# H_Bridge.net
KiCad netlist of a schematic drawn in Altium Designer
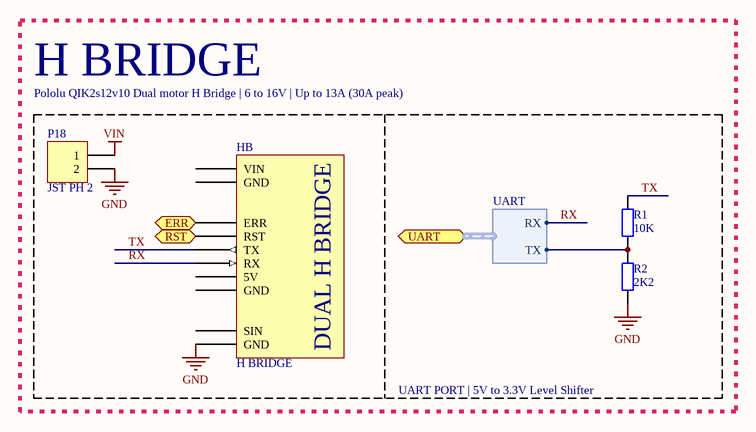
[diagram p0: H Bridge.SchDoc]

(export (version "E")
  (design (tool "Eeschema 10.0.6"))
  (components
    (comp (ref "HB")
      (value "H BRIDGE")
      (footprint "POLOLU-QIK-2S12V10-BOTTOM")
      (description "POLOLU QIK 2S12V10 DUAL H BRIDGE")
      (libsource (lib "CustomLibrary") (part "POLOLU-QIK-2S12V10"))
    )
    (comp (ref "P18")
      (value "JST PH 2")
      (footprint "B2B-PH-K")
      (libsource (lib "CustomLibrary") (part "JST PH 2"))
    )
    (comp (ref "R1") (value "10K") (footprint "RES1206") (libsource (lib "CustomLibrary") (part "RES")))
    (comp (ref "R2") (value "2K2") (footprint "RES1206") (libsource (lib "CustomLibrary") (part "RES")))
  )
  (nets
    (net (code "2") (name "/ERR") (class "Default")
      (node (ref "HB") (pin "ERR") (pinfunction "ERR_ERR") (pintype "passive"))
    )
    (net (code "3") (name "/RST") (class "Default")
      (node (ref "HB") (pin "RST") (pinfunction "RST_RST") (pintype "passive"))
    )
    (net (code "4") (name "/RX") (class "Default")
      (node (ref "HB") (pin "RX") (pinfunction "RX_RX") (pintype "input"))
    )
    (net (code "5") (name "/TX") (class "Default")
      (node (ref "HB") (pin "TX") (pinfunction "TX_TX") (pintype "output"))
      (node (ref "R1") (pin "2") (pinfunction "2_2") (pintype "passive"))
    )
    (net (code "7") (name "GND") (class "Default")
      (node (ref "HB") (pin "GND3") (pinfunction "GND_GND3") (pintype "power_in"))
      (node (ref "P18") (pin "2") (pinfunction "2_2") (pintype "passive"))
      (node (ref "R2") (pin "1") (pinfunction "1_1") (pintype "passive"))
    )
    (net (code "8") (name "Net-(R1-Pad1)") (class "Default")
      (node (ref "R1") (pin "1") (pinfunction "1_1") (pintype "passive"))
      (node (ref "R2") (pin "2") (pinfunction "2_2") (pintype "passive"))
    )
    (net (code "9") (name "VIN") (class "Default")
      (node (ref "P18") (pin "1") (pinfunction "1_1") (pintype "passive"))
    )
    (net (code "10") (name "unconnected-(HB-GND-PadGND1)") (class "Default")
      (node (ref "HB") (pin "GND1") (pinfunction "GND_GND1") (pintype "power_in"))
    )
    (net (code "11") (name "unconnected-(HB-GND-PadGND2)") (class "Default")
      (node (ref "HB") (pin "GND2") (pinfunction "GND_GND2") (pintype "power_in"))
    )
    (net (code "12") (name "unconnected-(HB-Pad5V)") (class "Default")
      (node (ref "HB") (pin "5V") (pinfunction "5V_5V") (pintype "passive"))
    )
    (net (code "13") (name "unconnected-(HB-PadSIN)") (class "Default")
      (node (ref "HB") (pin "SIN") (pinfunction "SIN_SIN") (pintype "passive"))
    )
    (net (code "14") (name "unconnected-(HB-PadVIN)") (class "Default")
      (node (ref "HB") (pin "VIN") (pinfunction "VIN_VIN") (pintype "power_in"))
    )
  )
)
